# Auxillary_Supply.net
KiCad netlist of a schematic drawn in Altium Designer
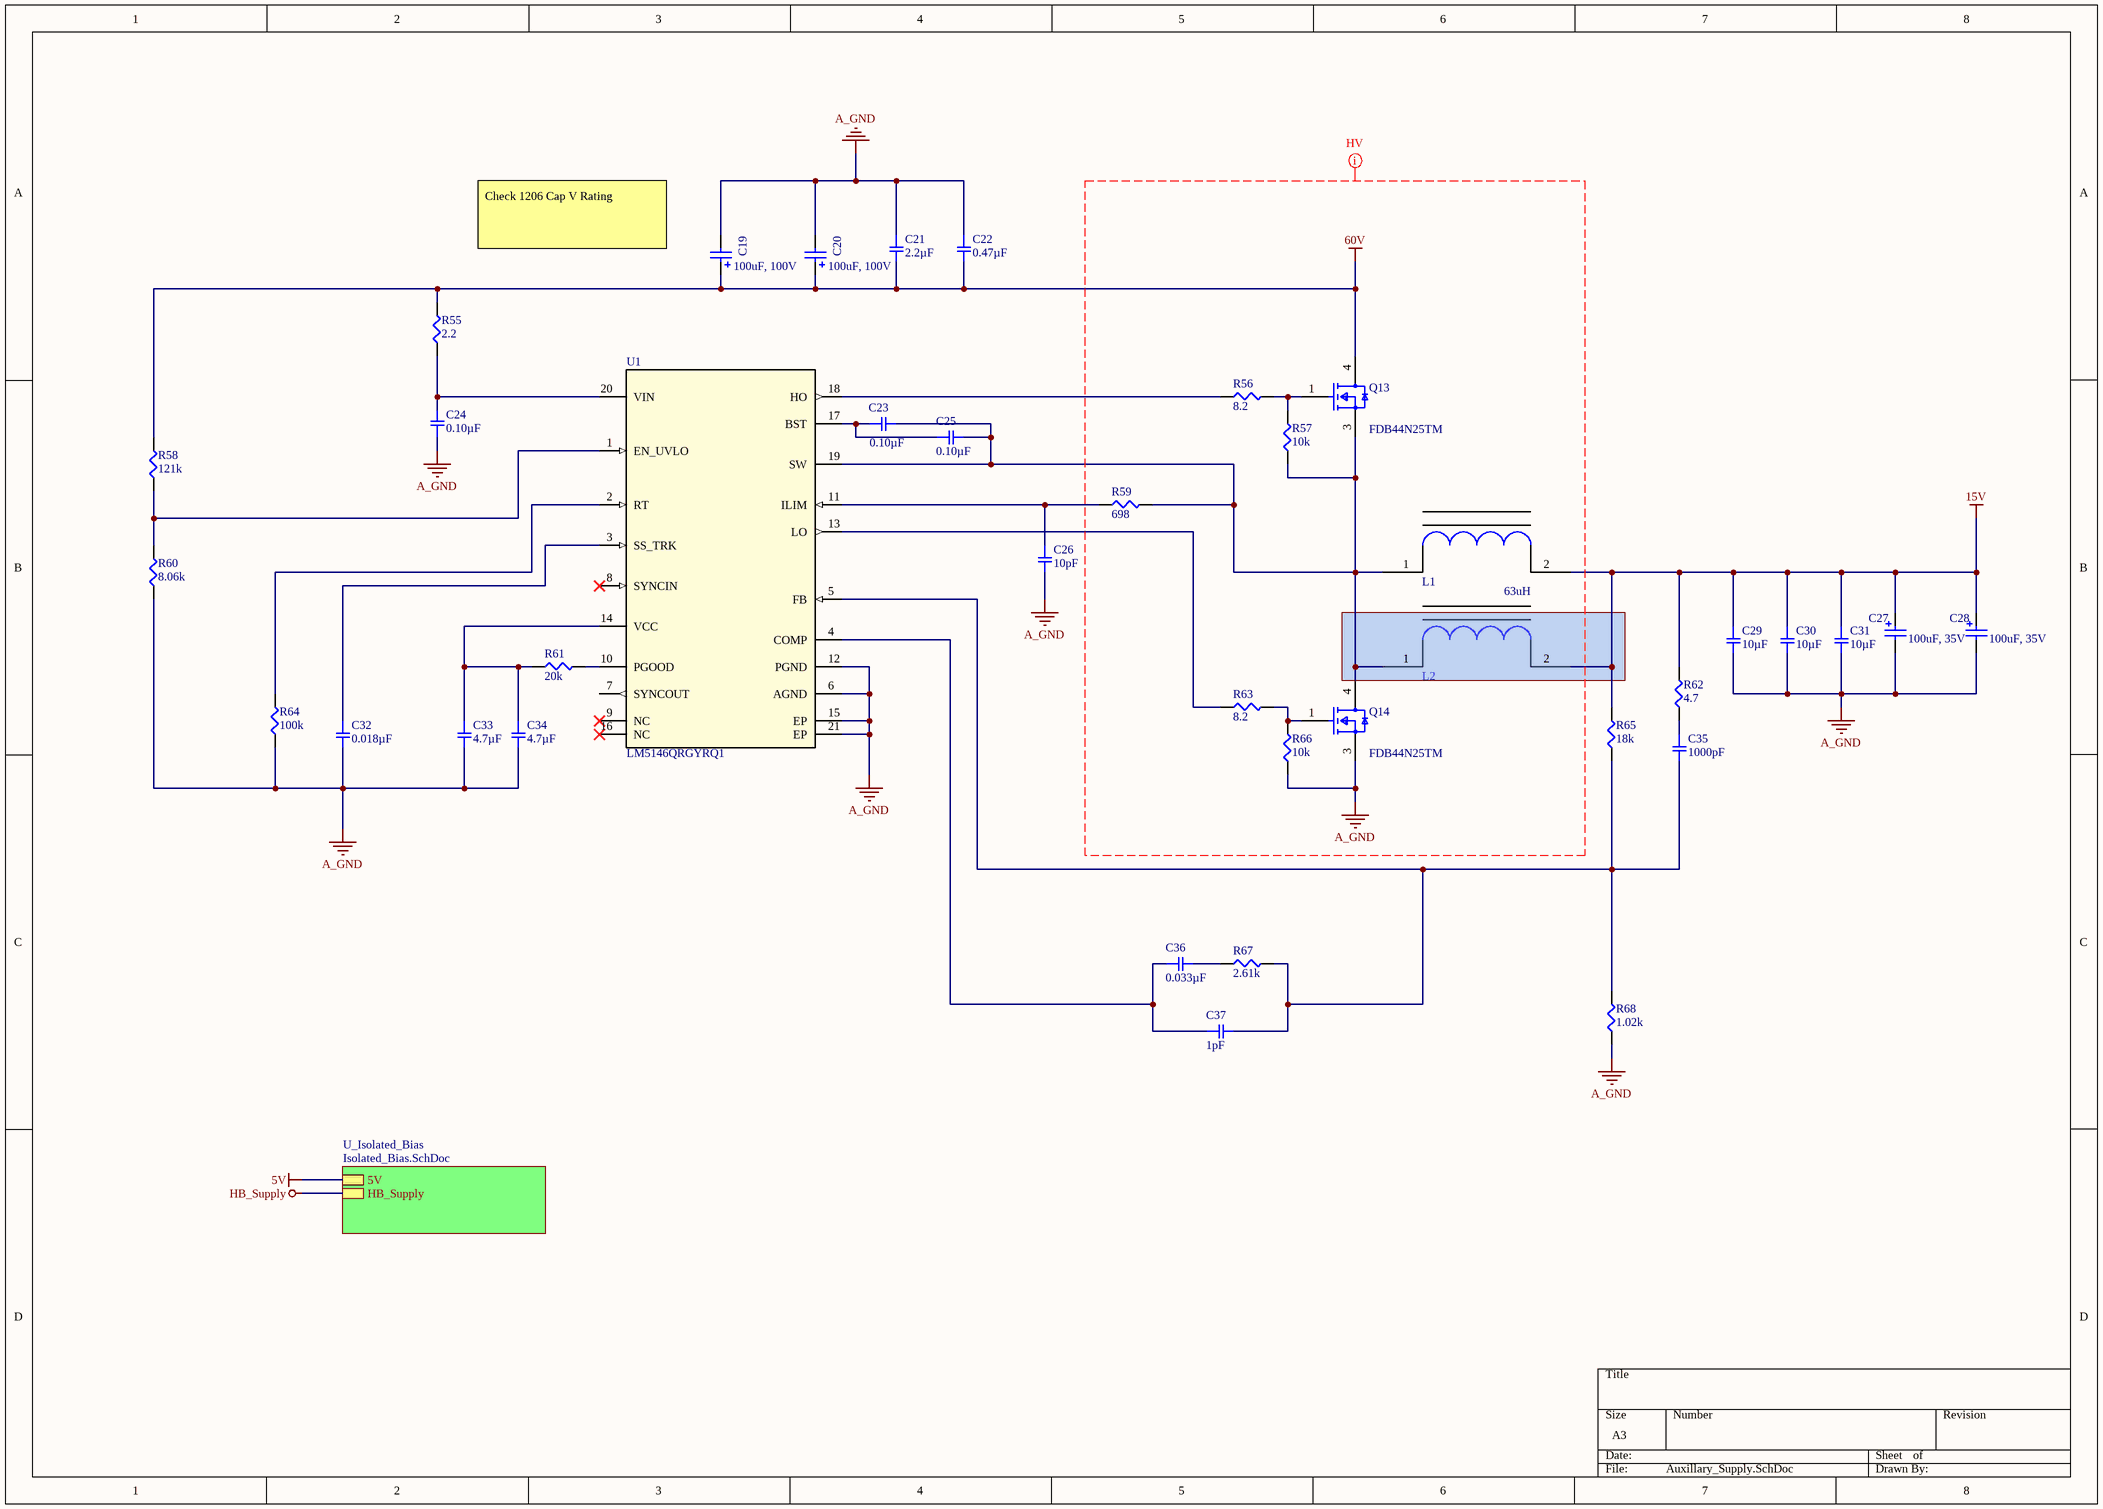
[diagram p0: Auxillary_Supply.SchDoc]

(export (version "E")
  (design (tool "Eeschema 10.0.6"))
  (components
    (comp (ref "C19")
      (value "100uF, 100V")
      (footprint "WCAP-ATUL_10x25")
      (description "WCAP-ATUL THT Aluminum Electrolytic Capacitors, D10mm x L25mm, 100uF, +/-20%, 100VDC")
      (fields (field (name "PART NUMBER") "860040875005") (field (name "PUBLISHER") "Wurth Elektronik"))
      (libsource (lib "Altium_WCAP-ATUL_rev19a") (part "860040875005"))
    )
    (comp (ref "C20")
      (value "100uF, 100V")
      (footprint "WCAP-ATUL_10x25")
      (description "WCAP-ATUL THT Aluminum Electrolytic Capacitors, D10mm x L25mm, 100uF, +/-20%, 100VDC")
      (fields (field (name "PART NUMBER") "860040875005") (field (name "PUBLISHER") "Wurth Elektronik"))
      (libsource (lib "Altium_WCAP-ATUL_rev19a") (part "860040875005"))
    )
    (comp (ref "C21")
      (value "2.2µF")
      (footprint "SMD-1210C")
      (description "CAP CER 2.2UF 100V X7R 1210")
      (fields
        (field (name "DIGI-KEY PART NUMBER") "490-5840-1-ND")
        (field (name "PART NUMBER") "GCJ32DR72A225KA01L")
      )
      (libsource (lib "capacitor_murata_1210") (part "GCJ32DR72A225KA01L"))
    )
    (comp (ref "C22")
      (value "0.47µF")
      (footprint "SMD-1206C")
      (description "CAP CER 0.47UF 100V X7R 1206")
      (fields
        (field (name "DIGI-KEY PART NUMBER") "490-11647-1-ND")
        (field (name "PART NUMBER") "GRM31MR72A474KA35L")
      )
      (libsource (lib "capacitor_murata_1206") (part "GRM31MR72A474KA35L"))
    )
    (comp (ref "C23")
      (value "0.10µF")
      (footprint "SMD-0805C")
      (description "CAP CER 0.1UF 25V X7R 0805")
      (fields
        (field (name "DIGI-KEY PART NUMBER") "490-1673-1-ND")
        (field (name "PART NUMBER") "GRM21BR71E104KA01L")
      )
      (libsource (lib "capacitor_murata_0805") (part "GRM21BR71E104KA01L"))
    )
    (comp (ref "C24")
      (value "0.10µF")
      (footprint "SMD-0805C")
      (description "CAP CER 0.1UF 25V X7R 0805")
      (fields
        (field (name "DIGI-KEY PART NUMBER") "490-1673-1-ND")
        (field (name "PART NUMBER") "GRM21BR71E104KA01L")
      )
      (libsource (lib "capacitor_murata_0805") (part "GRM21BR71E104KA01L"))
    )
    (comp (ref "C25")
      (value "0.10µF")
      (footprint "SMD-0805C")
      (description "CAP CER 0.1UF 25V X7R 0805")
      (fields
        (field (name "DIGI-KEY PART NUMBER") "490-1673-1-ND")
        (field (name "PART NUMBER") "GRM21BR71E104KA01L")
      )
      (libsource (lib "capacitor_murata_0805") (part "GRM21BR71E104KA01L"))
    )
    (comp (ref "C26")
      (value "10pF")
      (footprint "SMD-0805C")
      (description "CAP CER 10PF 100V NP0 0805")
      (fields
        (field (name "DIGI-KEY PART NUMBER") "490-6098-1-ND")
        (field (name "PART NUMBER") "GQM2195C2A100GB01D")
      )
      (libsource (lib "capacitor_murata_0805") (part "GQM2195C2A100GB01D"))
    )
    (comp (ref "C27")
      (value "100uF, 35V")
      (footprint "WCAP-ASLL_8x10.5")
      (description "WCAP-ASLL SMT Aluminum Electrolytic Capacitors, D8mm x L10.5mm, 100uF, +/-20%, 35VDC")
      (fields (field (name "PART NUMBER") "865060553006") (field (name "PUBLISHER") "Wurth Elektronik"))
      (libsource (lib "Altium_WCAP-ASLL_SMD") (part "865060553006"))
    )
    (comp (ref "C28")
      (value "100uF, 35V")
      (footprint "WCAP-ASLL_8x10.5")
      (description "WCAP-ASLL SMT Aluminum Electrolytic Capacitors, D8mm x L10.5mm, 100uF, +/-20%, 35VDC")
      (fields (field (name "PART NUMBER") "865060553006") (field (name "PUBLISHER") "Wurth Elektronik"))
      (libsource (lib "Altium_WCAP-ASLL_SMD") (part "865060553006"))
    )
    (comp (ref "C29")
      (value "10µF")
      (footprint "SMD-1210C")
      (description "CAP CER 10UF 25V X5R 1210")
      (fields
        (field (name "DIGI-KEY PART NUMBER") "490-6530-1-ND")
        (field (name "PART NUMBER") "GRM32DR61E106MA12L")
      )
      (libsource (lib "capacitor_murata_1210") (part "GRM32DR61E106MA12L"))
    )
    (comp (ref "C30")
      (value "10µF")
      (footprint "SMD-1206C")
      (description "CAP CER 10UF 25V X7R 1206")
      (fields
        (field (name "DIGI-KEY PART NUMBER") "490-6519-1-ND")
        (field (name "PART NUMBER") "GRM31CR71E106MA12L")
      )
      (libsource (lib "capacitor_murata_1206") (part "GRM31CR71E106MA12L"))
    )
    (comp (ref "C31")
      (value "10µF")
      (footprint "SMD-1206C")
      (description "CAP CER 10UF 25V X7R 1206")
      (fields
        (field (name "DIGI-KEY PART NUMBER") "490-6519-1-ND")
        (field (name "PART NUMBER") "GRM31CR71E106MA12L")
      )
      (libsource (lib "capacitor_murata_1206") (part "GRM31CR71E106MA12L"))
    )
    (comp (ref "C32")
      (value "0.018µF")
      (footprint "SMD-0805C")
      (description "CAP CER 0.018UF 100V X7R 0805")
      (fields
        (field (name "DIGI-KEY PART NUMBER") "490-1657-1-ND")
        (field (name "PART NUMBER") "GRM21BR72A183KA01L")
      )
      (libsource (lib "capacitor_murata_0805") (part "GRM21BR72A183KA01L"))
    )
    (comp (ref "C33")
      (value "4.7µF")
      (footprint "SMD-0805C")
      (description "CAP CER 4.7UF 16V X7R 0805")
      (fields
        (field (name "DIGI-KEY PART NUMBER") "490-10557-1-ND")
        (field (name "PART NUMBER") "GCJ21BR71C475KA01L")
      )
      (libsource (lib "capacitor_murata_0805") (part "GCJ21BR71C475KA01L"))
    )
    (comp (ref "C34")
      (value "4.7µF")
      (footprint "SMD-0805C")
      (description "CAP CER 4.7UF 16V X7R 0805")
      (fields
        (field (name "DIGI-KEY PART NUMBER") "490-10557-1-ND")
        (field (name "PART NUMBER") "GCJ21BR71C475KA01L")
      )
      (libsource (lib "capacitor_murata_0805") (part "GCJ21BR71C475KA01L"))
    )
    (comp (ref "C35")
      (value "1000pF")
      (footprint "SMD-0805C")
      (description "CAP CER 1000PF 50V X7R 0805")
      (fields
        (field (name "DIGI-KEY PART NUMBER") "490-5813-1-ND")
        (field (name "PART NUMBER") "GCJ216R71H102KA01D")
      )
      (libsource (lib "capacitor_murata_0805") (part "GCJ216R71H102KA01D"))
    )
    (comp (ref "C36")
      (value "0.033µF")
      (footprint "SMD-0805C")
      (description "CAP CER 0.033UF 50V X7R 0805")
      (fields
        (field (name "DIGI-KEY PART NUMBER") "490-5846-1-ND")
        (field (name "PART NUMBER") "GCJ219R71H333KA01D")
      )
      (libsource (lib "capacitor_murata_0805") (part "GCJ219R71H333KA01D"))
    )
    (comp (ref "C37")
      (value "1pF")
      (footprint "SMD-0805C")
      (description "CAP CER 1PF 100V NP0 0805")
      (fields
        (field (name "DIGI-KEY PART NUMBER") "490-6099-1-ND")
        (field (name "PART NUMBER") "GQM2195C2A1R0BB01D")
      )
      (libsource (lib "capacitor_murata_0805") (part "GQM2195C2A1R0BB01D"))
    )
    (comp (ref "L1")
      (value "63uH")
      (footprint "SRR1260")
      (fields (field (name "Comment") "Inductor"))
      (libsource (lib "NUCLEOG431RB-Custom-IN-A2212") (part "Inductor"))
    )
    (comp (ref "L2")
      (value "Inductor")
      (footprint "Inductor 25mm")
      (libsource (lib "NUCLEOG431RB-Custom-IN-A2212") (part "Inductor"))
    )
    (comp (ref "Q13")
      (value "FDB44N25TM")
      (footprint "FP-418AJ-MFG")
      (description "MOSFET N-CH 250V 44A D2PAK")
      (fields
        (field (name "OCTOPART") "https://octopart.com/fdb44n25tm-on+semiconductor-84325676")
        (field (name "MANUFACTURER") "ON Semi")
      )
      (libsource (lib "Altium Content Vault") (part "6cfb7a7e3182ee66171b2134aae8142"))
    )
    (comp (ref "Q14")
      (value "FDB44N25TM")
      (footprint "FP-418AJ-MFG")
      (description "MOSFET N-CH 250V 44A D2PAK")
      (fields
        (field (name "OCTOPART") "https://octopart.com/fdb44n25tm-on+semiconductor-84325676")
        (field (name "MANUFACTURER") "ON Semi")
      )
      (libsource (lib "Altium Content Vault") (part "6cfb7a7e3182ee66171b2134aae8142"))
    )
    (comp (ref "R55")
      (value "2.2")
      (footprint "SMD-0805-RES")
      (description "RES SMD 2.2 OHM 1% 1/3W 0805")
      (fields (field (name "PART NUMBER") "ERJ-6BQF2R2V") (field (name "DIGI-KEY PART NUMBER") "P17504CT-ND"))
      (libsource (lib "Panasonic_ERJ_0805") (part "ERJ-6BQF2R2V"))
    )
    (comp (ref "R56")
      (value "8.2")
      (footprint "SMD-0805-RES")
      (description "RES SMD 8.2 OHM 1% 1/3W 0805")
      (fields (field (name "PART NUMBER") "ERJ-6BQF8R2V") (field (name "DIGI-KEY PART NUMBER") "P17514CT-ND"))
      (libsource (lib "Panasonic_ERJ_0805") (part "ERJ-6BQF8R2V"))
    )
    (comp (ref "R57")
      (value "10k")
      (footprint "SMD-0805-RES")
      (description "RES SMD 10K OHM 1% 1/8W 0805")
      (fields
        (field (name "PART NUMBER") "ERJ-6ENF1002V")
        (field (name "DIGI-KEY PART NUMBER") "P10.0KCCT-ND")
      )
      (libsource (lib "Panasonic_ERJ_0805") (part "ERJ-6ENF1002V"))
    )
    (comp (ref "R58")
      (value "121k")
      (footprint "SMD-0805-RES")
      (description "RES SMD 121K OHM 1% 1/8W 0805")
      (fields
        (field (name "PART NUMBER") "ERJ-6ENF1213V")
        (field (name "DIGI-KEY PART NUMBER") "P121KCCT-ND")
      )
      (libsource (lib "Panasonic_ERJ_0805") (part "ERJ-6ENF1213V"))
    )
    (comp (ref "R59")
      (value "698")
      (footprint "SMD-0805-RES")
      (description "RES SMD 698 OHM 1% 1/8W 0805")
      (fields (field (name "PART NUMBER") "ERJ-6ENF6980V") (field (name "DIGI-KEY PART NUMBER") "P698CCT-ND"))
      (libsource (lib "Panasonic_ERJ_0805") (part "ERJ-6ENF6980V"))
    )
    (comp (ref "R60")
      (value "8.06k")
      (footprint "SMD-0805-RES")
      (description "RES SMD 8.06K OHM 1% 1/8W 0805")
      (fields
        (field (name "PART NUMBER") "ERJ-6ENF8061V")
        (field (name "DIGI-KEY PART NUMBER") "P8.06KCCT-ND")
      )
      (libsource (lib "Panasonic_ERJ_0805") (part "ERJ-6ENF8061V"))
    )
    (comp (ref "R61")
      (value "20k")
      (footprint "SMD-0805-RES")
      (description "RES SMD 20K OHM 1% 1/8W 0805")
      (fields
        (field (name "PART NUMBER") "ERJ-6ENF2002V")
        (field (name "DIGI-KEY PART NUMBER") "P20.0KCCT-ND")
      )
      (libsource (lib "Panasonic_ERJ_0805") (part "ERJ-6ENF2002V"))
    )
    (comp (ref "R62")
      (value "4.7")
      (footprint "SMD-0805-RES")
      (description "RES SMD 4.7 OHM 1% 1/3W 0805")
      (fields (field (name "PART NUMBER") "ERJ-6BQF4R7V") (field (name "DIGI-KEY PART NUMBER") "P15995CT-ND"))
      (libsource (lib "Panasonic_ERJ_0805") (part "ERJ-6BQF4R7V"))
    )
    (comp (ref "R63")
      (value "8.2")
      (footprint "SMD-0805-RES")
      (description "RES SMD 8.2 OHM 1% 1/3W 0805")
      (fields (field (name "PART NUMBER") "ERJ-6BQF8R2V") (field (name "DIGI-KEY PART NUMBER") "P17514CT-ND"))
      (libsource (lib "Panasonic_ERJ_0805") (part "ERJ-6BQF8R2V"))
    )
    (comp (ref "R64")
      (value "100k")
      (footprint "SMD-0805-RES")
      (description "RES SMD 100K OHM 1% 1/8W 0805")
      (fields
        (field (name "PART NUMBER") "ERJ-6ENF1003V")
        (field (name "DIGI-KEY PART NUMBER") "P100KCCT-ND")
      )
      (libsource (lib "Panasonic_ERJ_0805") (part "ERJ-6ENF1003V"))
    )
    (comp (ref "R65")
      (value "18k")
      (footprint "SMD-0805-RES")
      (description "RES SMD 18K OHM 1% 1/8W 0805")
      (fields
        (field (name "PART NUMBER") "ERJ-6ENF1802V")
        (field (name "DIGI-KEY PART NUMBER") "P18.0KCCT-ND")
      )
      (libsource (lib "Panasonic_ERJ_0805") (part "ERJ-6ENF1802V"))
    )
    (comp (ref "R66")
      (value "10k")
      (footprint "SMD-0805-RES")
      (description "RES SMD 10K OHM 1% 1/8W 0805")
      (fields
        (field (name "PART NUMBER") "ERJ-6ENF1002V")
        (field (name "DIGI-KEY PART NUMBER") "P10.0KCCT-ND")
      )
      (libsource (lib "Panasonic_ERJ_0805") (part "ERJ-6ENF1002V"))
    )
    (comp (ref "R67")
      (value "2.61k")
      (footprint "SMD-0805-RES")
      (description "RES SMD 2.61K OHM 1% 1/8W 0805")
      (fields
        (field (name "PART NUMBER") "ERJ-6ENF2611V")
        (field (name "DIGI-KEY PART NUMBER") "P2.61KCCT-ND")
      )
      (libsource (lib "Panasonic_ERJ_0805") (part "ERJ-6ENF2611V"))
    )
    (comp (ref "R68")
      (value "1.02k")
      (footprint "SMD-0805-RES")
      (description "RES SMD 1.02K OHM 1% 1/8W 0805")
      (fields
        (field (name "PART NUMBER") "ERJ-6ENF1021V")
        (field (name "DIGI-KEY PART NUMBER") "P1.02KCCT-ND")
      )
      (libsource (lib "Panasonic_ERJ_0805") (part "ERJ-6ENF1021V"))
    )
    (comp (ref "U1")
      (value "LM5146QRGYRQ1")
      (footprint "QFN50P350X450X100_HS-21N")
      (description "Imported")
      (fields (field (name "MANUFACTURER") "Texas Instruments"))
      (libsource (lib "NUCLEOG431RB-Custom-IN-A2212") (part "LM5146QRGYRQ1"))
    )
  )
  (nets
    (net (code "2") (name "15V") (class "Default")
      (node (ref "C27") (pin "2") (pinfunction "P_2") (pintype "passive"))
      (node (ref "C28") (pin "2") (pinfunction "P_2") (pintype "passive"))
      (node (ref "C29") (pin "1") (pinfunction "1_1") (pintype "passive"))
      (node (ref "C30") (pin "1") (pinfunction "1_1") (pintype "passive"))
      (node (ref "C31") (pin "1") (pinfunction "1_1") (pintype "passive"))
      (node (ref "L1") (pin "2") (pinfunction "2_2") (pintype "passive"))
      (node (ref "L2") (pin "2") (pinfunction "2_2") (pintype "passive"))
      (node (ref "R62") (pin "2") (pinfunction "2_2") (pintype "passive"))
      (node (ref "R65") (pin "2") (pinfunction "2_2") (pintype "passive"))
    )
    (net (code "3") (name "60V") (class "Default")
      (node (ref "C19") (pin "2") (pinfunction "P_2") (pintype "passive"))
      (node (ref "C20") (pin "2") (pinfunction "P_2") (pintype "passive"))
      (node (ref "C21") (pin "2") (pinfunction "2_2") (pintype "passive"))
      (node (ref "C22") (pin "2") (pinfunction "2_2") (pintype "passive"))
      (node (ref "Q13") (pin "4") (pinfunction "D_4") (pintype "passive"))
      (node (ref "R55") (pin "2") (pinfunction "2_2") (pintype "passive"))
      (node (ref "R58") (pin "2") (pinfunction "2_2") (pintype "passive"))
    )
    (net (code "4") (name "A_GND") (class "Default")
      (node (ref "C19") (pin "1") (pinfunction "N_1") (pintype "passive"))
      (node (ref "C20") (pin "1") (pinfunction "N_1") (pintype "passive"))
      (node (ref "C21") (pin "1") (pinfunction "1_1") (pintype "passive"))
      (node (ref "C22") (pin "1") (pinfunction "1_1") (pintype "passive"))
      (node (ref "C24") (pin "1") (pinfunction "1_1") (pintype "passive"))
      (node (ref "C26") (pin "2") (pinfunction "2_2") (pintype "passive"))
      (node (ref "C27") (pin "1") (pinfunction "N_1") (pintype "passive"))
      (node (ref "C28") (pin "1") (pinfunction "N_1") (pintype "passive"))
      (node (ref "C29") (pin "2") (pinfunction "2_2") (pintype "passive"))
      (node (ref "C30") (pin "2") (pinfunction "2_2") (pintype "passive"))
      (node (ref "C31") (pin "2") (pinfunction "2_2") (pintype "passive"))
      (node (ref "C32") (pin "2") (pinfunction "2_2") (pintype "passive"))
      (node (ref "C33") (pin "2") (pinfunction "2_2") (pintype "passive"))
      (node (ref "C34") (pin "2") (pinfunction "2_2") (pintype "passive"))
      (node (ref "Q14") (pin "3") (pinfunction "S_3") (pintype "passive"))
      (node (ref "R60") (pin "1") (pinfunction "1_1") (pintype "passive"))
      (node (ref "R64") (pin "1") (pinfunction "1_1") (pintype "passive"))
      (node (ref "R66") (pin "1") (pinfunction "1_1") (pintype "passive"))
      (node (ref "R68") (pin "1") (pinfunction "1_1") (pintype "passive"))
      (node (ref "U1") (pin "12") (pinfunction "PGND_12") (pintype "power_in"))
      (node (ref "U1") (pin "15") (pinfunction "EP_15") (pintype "power_in"))
      (node (ref "U1") (pin "21") (pinfunction "EP_21") (pintype "power_in"))
      (node (ref "U1") (pin "6") (pinfunction "AGND_6") (pintype "power_in"))
    )
    (net (code "6") (name "Net-(C35-Pad1)") (class "Default")
      (node (ref "C35") (pin "1") (pinfunction "1_1") (pintype "passive"))
      (node (ref "R62") (pin "1") (pinfunction "1_1") (pintype "passive"))
    )
    (net (code "7") (name "Net-(C36-Pad2)") (class "Default")
      (node (ref "C36") (pin "2") (pinfunction "2_2") (pintype "passive"))
      (node (ref "R67") (pin "1") (pinfunction "1_1") (pintype "passive"))
    )
    (net (code "8") (name "Net-(Q13-G)") (class "Default")
      (node (ref "Q13") (pin "1") (pinfunction "G_1") (pintype "passive"))
      (node (ref "R56") (pin "2") (pinfunction "2_2") (pintype "passive"))
      (node (ref "R57") (pin "2") (pinfunction "2_2") (pintype "passive"))
    )
    (net (code "9") (name "Net-(Q13-S)") (class "Default")
      (node (ref "C23") (pin "2") (pinfunction "2_2") (pintype "passive"))
      (node (ref "C25") (pin "2") (pinfunction "2_2") (pintype "passive"))
      (node (ref "L1") (pin "1") (pinfunction "1_1") (pintype "passive"))
      (node (ref "L2") (pin "1") (pinfunction "1_1") (pintype "passive"))
      (node (ref "Q13") (pin "3") (pinfunction "S_3") (pintype "passive"))
      (node (ref "Q14") (pin "4") (pinfunction "D_4") (pintype "passive"))
      (node (ref "R57") (pin "1") (pinfunction "1_1") (pintype "passive"))
      (node (ref "R59") (pin "2") (pinfunction "2_2") (pintype "passive"))
      (node (ref "U1") (pin "19") (pinfunction "SW_19") (pintype "power_in"))
    )
    (net (code "10") (name "Net-(Q14-G)") (class "Default")
      (node (ref "Q14") (pin "1") (pinfunction "G_1") (pintype "passive"))
      (node (ref "R63") (pin "2") (pinfunction "2_2") (pintype "passive"))
      (node (ref "R66") (pin "2") (pinfunction "2_2") (pintype "passive"))
    )
    (net (code "11") (name "Net-(U1-BST)") (class "Default")
      (node (ref "C23") (pin "1") (pinfunction "1_1") (pintype "passive"))
      (node (ref "C25") (pin "1") (pinfunction "1_1") (pintype "passive"))
      (node (ref "U1") (pin "17") (pinfunction "BST_17") (pintype "passive"))
    )
    (net (code "12") (name "Net-(U1-COMP)") (class "Default")
      (node (ref "C36") (pin "1") (pinfunction "1_1") (pintype "passive"))
      (node (ref "C37") (pin "1") (pinfunction "1_1") (pintype "passive"))
      (node (ref "U1") (pin "4") (pinfunction "COMP_4") (pintype "passive"))
    )
    (net (code "13") (name "Net-(U1-EN_UVLO)") (class "Default")
      (node (ref "R58") (pin "1") (pinfunction "1_1") (pintype "passive"))
      (node (ref "R60") (pin "2") (pinfunction "2_2") (pintype "passive"))
      (node (ref "U1") (pin "1") (pinfunction "EN_UVLO_1") (pintype "input"))
    )
    (net (code "14") (name "Net-(U1-FB)") (class "Default")
      (node (ref "C35") (pin "2") (pinfunction "2_2") (pintype "passive"))
      (node (ref "C37") (pin "2") (pinfunction "2_2") (pintype "passive"))
      (node (ref "R65") (pin "1") (pinfunction "1_1") (pintype "passive"))
      (node (ref "R67") (pin "2") (pinfunction "2_2") (pintype "passive"))
      (node (ref "R68") (pin "2") (pinfunction "2_2") (pintype "passive"))
      (node (ref "U1") (pin "5") (pinfunction "FB_5") (pintype "input"))
    )
    (net (code "15") (name "Net-(U1-HO)") (class "Default")
      (node (ref "R56") (pin "1") (pinfunction "1_1") (pintype "passive"))
      (node (ref "U1") (pin "18") (pinfunction "HO_18") (pintype "output"))
    )
    (net (code "16") (name "Net-(U1-ILIM)") (class "Default")
      (node (ref "C26") (pin "1") (pinfunction "1_1") (pintype "passive"))
      (node (ref "R59") (pin "1") (pinfunction "1_1") (pintype "passive"))
      (node (ref "U1") (pin "11") (pinfunction "ILIM_11") (pintype "input"))
    )
    (net (code "17") (name "Net-(U1-LO)") (class "Default")
      (node (ref "R63") (pin "1") (pinfunction "1_1") (pintype "passive"))
      (node (ref "U1") (pin "13") (pinfunction "LO_13") (pintype "output"))
    )
    (net (code "18") (name "Net-(U1-PGOOD)") (class "Default")
      (node (ref "R61") (pin "2") (pinfunction "2_2") (pintype "passive"))
      (node (ref "U1") (pin "10") (pinfunction "PGOOD_10") (pintype "open_collector"))
    )
    (net (code "19") (name "Net-(U1-RT)") (class "Default")
      (node (ref "R64") (pin "2") (pinfunction "2_2") (pintype "passive"))
      (node (ref "U1") (pin "2") (pinfunction "RT_2") (pintype "input"))
    )
    (net (code "20") (name "Net-(U1-SS_TRK)") (class "Default")
      (node (ref "C32") (pin "1") (pinfunction "1_1") (pintype "passive"))
      (node (ref "U1") (pin "3") (pinfunction "SS_TRK_3") (pintype "input"))
    )
    (net (code "21") (name "Net-(U1-VCC)") (class "Default")
      (node (ref "C33") (pin "1") (pinfunction "1_1") (pintype "passive"))
      (node (ref "C34") (pin "1") (pinfunction "1_1") (pintype "passive"))
      (node (ref "R61") (pin "1") (pinfunction "1_1") (pintype "passive"))
      (node (ref "U1") (pin "14") (pinfunction "VCC_14") (pintype "power_in"))
    )
    (net (code "22") (name "Net-(U1-VIN)") (class "Default")
      (node (ref "C24") (pin "2") (pinfunction "2_2") (pintype "passive"))
      (node (ref "R55") (pin "1") (pinfunction "1_1") (pintype "passive"))
      (node (ref "U1") (pin "20") (pinfunction "VIN_20") (pintype "power_in"))
    )
    (net (code "23") (name "unconnected-(U1-NC-Pad9)") (class "Default")
      (node (ref "U1") (pin "9") (pinfunction "NC_9") (pintype "passive+no_connect"))
    )
    (net (code "24") (name "unconnected-(U1-NC-Pad16)") (class "Default")
      (node (ref "U1") (pin "16") (pinfunction "NC_16") (pintype "passive+no_connect"))
    )
    (net (code "25") (name "unconnected-(U1-SYNCIN-Pad8)") (class "Default")
      (node (ref "U1") (pin "8") (pinfunction "SYNCIN_8") (pintype "input+no_connect"))
    )
    (net (code "26") (name "unconnected-(U1-SYNCOUT-Pad7)") (class "Default")
      (node (ref "U1") (pin "7") (pinfunction "SYNCOUT_7") (pintype "output"))
    )
  )
)
